# vn210-shield.net
KiCad netlist of a schematic drawn in EAGLE
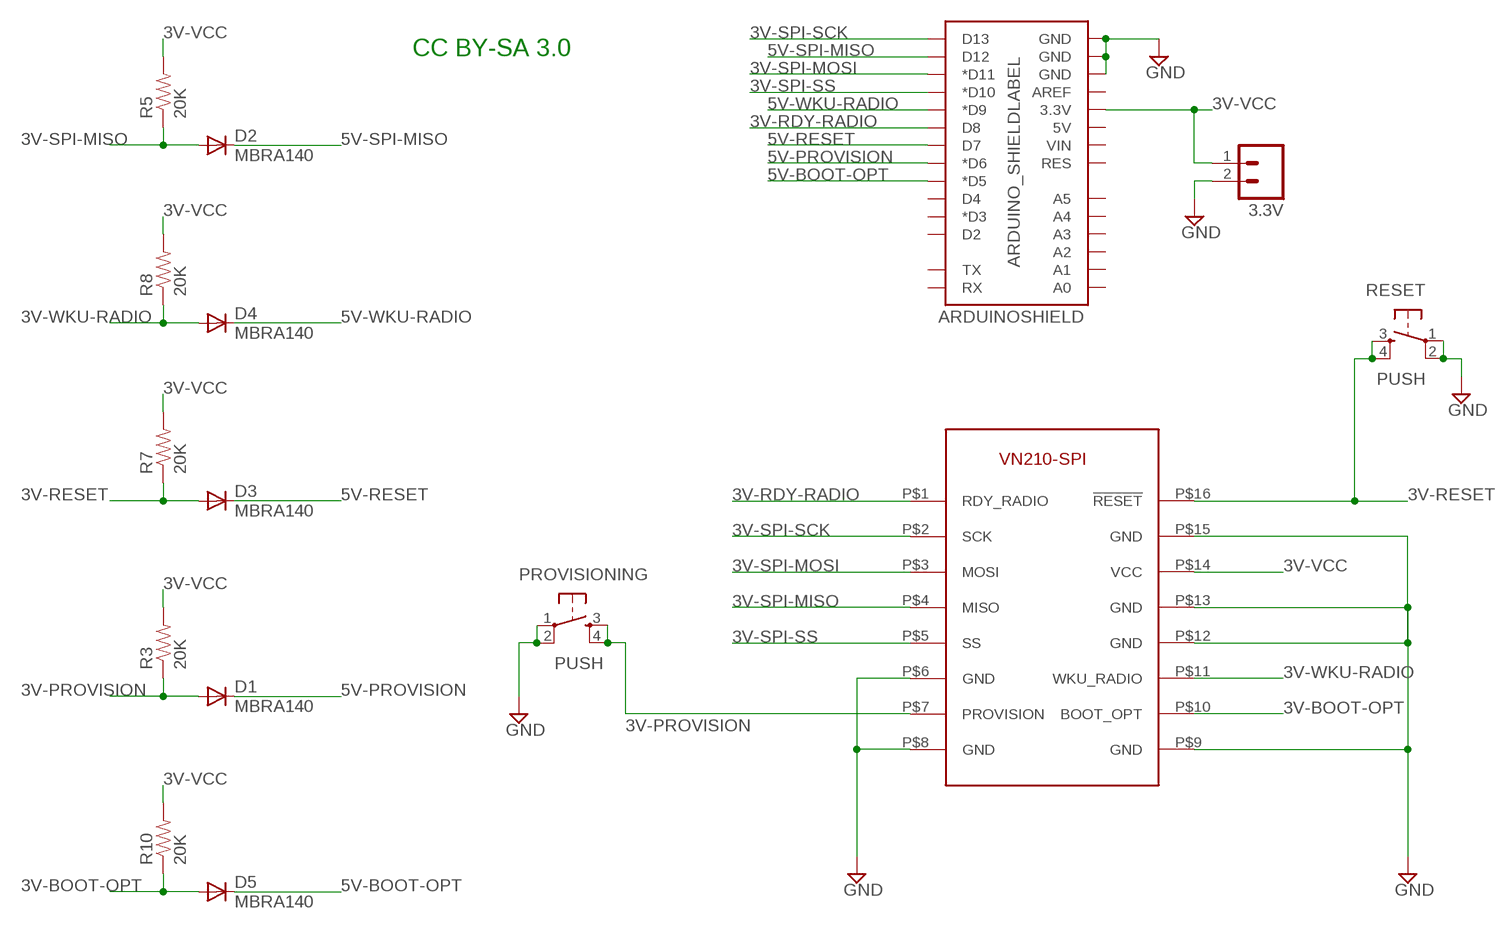
[diagram p0: schematic, sheet 1]

(export (version "E")
  (design (tool "Eeschema 10.0.6"))
  (components
    (comp (ref "3.3V")
      (value "M02LOCK")
      (footprint "eagle-import:1X02_LOCK")
      (libsource (lib "eagle-import") (part "M02LOCK"))
    )
    (comp (ref "ARDUINOSHIELD")
      (value "ARDUINO_SHIELDLABEL")
      (footprint "eagle-import:DUEMILANOVE_SHIELD")
      (libsource (lib "eagle-import") (part "ARDUINO_SHIELDLABEL"))
    )
    (comp (ref "D1")
      (value "MBRA140")
      (footprint "eagle-import:SMA-DIODE_ALT")
      (libsource (lib "eagle-import") (part "DIODESMA-ALT"))
    )
    (comp (ref "D2")
      (value "MBRA140")
      (footprint "eagle-import:SMA-DIODE_ALT")
      (libsource (lib "eagle-import") (part "DIODESMA-ALT"))
    )
    (comp (ref "D3")
      (value "MBRA140")
      (footprint "eagle-import:SMA-DIODE_ALT")
      (libsource (lib "eagle-import") (part "DIODESMA-ALT"))
    )
    (comp (ref "D4")
      (value "MBRA140")
      (footprint "eagle-import:SMA-DIODE_ALT")
      (libsource (lib "eagle-import") (part "DIODESMA-ALT"))
    )
    (comp (ref "D5")
      (value "MBRA140")
      (footprint "eagle-import:SMA-DIODE_ALT")
      (libsource (lib "eagle-import") (part "DIODESMA-ALT"))
    )
    (comp (ref "PROVISIONING")
      (value "PUSH")
      (footprint "eagle-import:TACTILE-PTH")
      (libsource (lib "eagle-import") (part "TAC_SWITCHPTH"))
    )
    (comp (ref "R3")
      (value "20K")
      (footprint "eagle-import:1206")
      (libsource (lib "eagle-import") (part "RESISTOR1206"))
    )
    (comp (ref "R5")
      (value "20K")
      (footprint "eagle-import:1206")
      (libsource (lib "eagle-import") (part "RESISTOR1206"))
    )
    (comp (ref "R7")
      (value "20K")
      (footprint "eagle-import:1206")
      (libsource (lib "eagle-import") (part "RESISTOR1206"))
    )
    (comp (ref "R8")
      (value "20K")
      (footprint "eagle-import:1206")
      (libsource (lib "eagle-import") (part "RESISTOR1206"))
    )
    (comp (ref "R10")
      (value "20K")
      (footprint "eagle-import:1206")
      (libsource (lib "eagle-import") (part "RESISTOR1206"))
    )
    (comp (ref "RESET")
      (value "PUSH")
      (footprint "eagle-import:TACTILE-PTH")
      (libsource (lib "eagle-import") (part "TAC_SWITCHPTH"))
    )
    (comp (ref "U$1")
      (value "VN210-BREAKOUT")
      (footprint "eagle-import:VN210-BREAKOUT")
      (libsource (lib "eagle-import") (part "VN210-BREAKOUT"))
    )
  )
  (nets
    (net (code "1") (name "/3V-BOOT-OPT") (class "Default")
      (node (ref "D5") (pin "A") (pinfunction "A_A") (pintype "passive"))
      (node (ref "R10") (pin "1") (pinfunction "1_1") (pintype "passive"))
      (node (ref "U$1") (pin "P$10") (pinfunction "BOOT_OPT_P$10") (pintype "bidirectional"))
    )
    (net (code "2") (name "/3V-PROVISION") (class "Default")
      (node (ref "D1") (pin "A") (pinfunction "A_A") (pintype "passive"))
      (node (ref "PROVISIONING") (pin "3") (pinfunction "3_3") (pintype "passive"))
      (node (ref "PROVISIONING") (pin "4") (pinfunction "4_4") (pintype "passive"))
      (node (ref "R3") (pin "1") (pinfunction "1_1") (pintype "passive"))
      (node (ref "U$1") (pin "P$7") (pinfunction "PROVISION_P$7") (pintype "bidirectional"))
    )
    (net (code "3") (name "/3V-RDY-RADIO") (class "Default")
      (node (ref "ARDUINOSHIELD") (pin "D8") (pinfunction "D8_D8") (pintype "bidirectional"))
      (node (ref "U$1") (pin "P$1") (pinfunction "RDY_RADIO_P$1") (pintype "bidirectional"))
    )
    (net (code "4") (name "/3V-RESET") (class "Default")
      (node (ref "D3") (pin "A") (pinfunction "A_A") (pintype "passive"))
      (node (ref "R7") (pin "1") (pinfunction "1_1") (pintype "passive"))
      (node (ref "RESET") (pin "3") (pinfunction "3_3") (pintype "passive"))
      (node (ref "RESET") (pin "4") (pinfunction "4_4") (pintype "passive"))
      (node (ref "U$1") (pin "P$16") (pinfunction "~{RESET}_P$16") (pintype "bidirectional"))
    )
    (net (code "5") (name "/3V-SPI-MISO") (class "Default")
      (node (ref "D2") (pin "A") (pinfunction "A_A") (pintype "passive"))
      (node (ref "R5") (pin "1") (pinfunction "1_1") (pintype "passive"))
      (node (ref "U$1") (pin "P$4") (pinfunction "MISO_P$4") (pintype "bidirectional"))
    )
    (net (code "6") (name "/3V-SPI-MOSI") (class "Default")
      (node (ref "ARDUINOSHIELD") (pin "D11") (pinfunction "*D11_D11") (pintype "bidirectional"))
      (node (ref "U$1") (pin "P$3") (pinfunction "MOSI_P$3") (pintype "bidirectional"))
    )
    (net (code "7") (name "/3V-SPI-SCK") (class "Default")
      (node (ref "ARDUINOSHIELD") (pin "D13") (pinfunction "D13_D13") (pintype "bidirectional"))
      (node (ref "U$1") (pin "P$2") (pinfunction "SCK_P$2") (pintype "bidirectional"))
    )
    (net (code "8") (name "/3V-SPI-SS") (class "Default")
      (node (ref "ARDUINOSHIELD") (pin "D10") (pinfunction "*D10_D10") (pintype "bidirectional"))
      (node (ref "U$1") (pin "P$5") (pinfunction "SS_P$5") (pintype "bidirectional"))
    )
    (net (code "9") (name "/3V-VCC") (class "Default")
      (node (ref "3.3V") (pin "1") (pinfunction "1_1") (pintype "passive"))
      (node (ref "ARDUINOSHIELD") (pin "3.3V") (pinfunction "3.3V_3.3V") (pintype "bidirectional"))
      (node (ref "R10") (pin "2") (pinfunction "2_2") (pintype "passive"))
      (node (ref "R3") (pin "2") (pinfunction "2_2") (pintype "passive"))
      (node (ref "R5") (pin "2") (pinfunction "2_2") (pintype "passive"))
      (node (ref "R7") (pin "2") (pinfunction "2_2") (pintype "passive"))
      (node (ref "R8") (pin "2") (pinfunction "2_2") (pintype "passive"))
      (node (ref "U$1") (pin "P$14") (pinfunction "VCC_P$14") (pintype "bidirectional"))
    )
    (net (code "10") (name "/3V-WKU-RADIO") (class "Default")
      (node (ref "D4") (pin "A") (pinfunction "A_A") (pintype "passive"))
      (node (ref "R8") (pin "1") (pinfunction "1_1") (pintype "passive"))
      (node (ref "U$1") (pin "P$11") (pinfunction "WKU_RADIO_P$11") (pintype "bidirectional"))
    )
    (net (code "11") (name "/5V-BOOT-OPT") (class "Default")
      (node (ref "ARDUINOSHIELD") (pin "D5") (pinfunction "*D5_D5") (pintype "bidirectional"))
      (node (ref "D5") (pin "C") (pinfunction "C_C") (pintype "passive"))
    )
    (net (code "12") (name "/5V-PROVISION") (class "Default")
      (node (ref "ARDUINOSHIELD") (pin "D6") (pinfunction "*D6_D6") (pintype "bidirectional"))
      (node (ref "D1") (pin "C") (pinfunction "C_C") (pintype "passive"))
    )
    (net (code "13") (name "/5V-RESET") (class "Default")
      (node (ref "ARDUINOSHIELD") (pin "D7") (pinfunction "D7_D7") (pintype "bidirectional"))
      (node (ref "D3") (pin "C") (pinfunction "C_C") (pintype "passive"))
    )
    (net (code "14") (name "/5V-SPI-MISO") (class "Default")
      (node (ref "ARDUINOSHIELD") (pin "D12") (pinfunction "D12_D12") (pintype "bidirectional"))
      (node (ref "D2") (pin "C") (pinfunction "C_C") (pintype "passive"))
    )
    (net (code "15") (name "/5V-WKU-RADIO") (class "Default")
      (node (ref "ARDUINOSHIELD") (pin "D9") (pinfunction "*D9_D9") (pintype "bidirectional"))
      (node (ref "D4") (pin "C") (pinfunction "C_C") (pintype "passive"))
    )
    (net (code "16") (name "GND") (class "Default")
      (node (ref "3.3V") (pin "2") (pinfunction "2_2") (pintype "passive"))
      (node (ref "ARDUINOSHIELD") (pin "GND@0") (pinfunction "GND_GND@0") (pintype "bidirectional"))
      (node (ref "ARDUINOSHIELD") (pin "GND@1") (pinfunction "GND_GND@1") (pintype "bidirectional"))
      (node (ref "ARDUINOSHIELD") (pin "GND@2") (pinfunction "GND_GND@2") (pintype "bidirectional"))
      (node (ref "PROVISIONING") (pin "1") (pinfunction "1_1") (pintype "passive"))
      (node (ref "PROVISIONING") (pin "2") (pinfunction "2_2") (pintype "passive"))
      (node (ref "RESET") (pin "1") (pinfunction "1_1") (pintype "passive"))
      (node (ref "RESET") (pin "2") (pinfunction "2_2") (pintype "passive"))
      (node (ref "U$1") (pin "P$12") (pinfunction "GND_P$12") (pintype "bidirectional"))
      (node (ref "U$1") (pin "P$13") (pinfunction "GND_P$13") (pintype "bidirectional"))
      (node (ref "U$1") (pin "P$15") (pinfunction "GND_P$15") (pintype "bidirectional"))
      (node (ref "U$1") (pin "P$6") (pinfunction "GND_P$6") (pintype "bidirectional"))
      (node (ref "U$1") (pin "P$8") (pinfunction "GND_P$8") (pintype "bidirectional"))
      (node (ref "U$1") (pin "P$9") (pinfunction "GND_P$9") (pintype "bidirectional"))
    )
    (net (code "17") (name "unconnected-(ARDUINOSHIELD-*D3-PadD3)") (class "Default")
      (node (ref "ARDUINOSHIELD") (pin "D3") (pinfunction "*D3_D3") (pintype "bidirectional"))
    )
    (net (code "18") (name "unconnected-(ARDUINOSHIELD-Pad5V)") (class "Default")
      (node (ref "ARDUINOSHIELD") (pin "5V") (pinfunction "5V_5V") (pintype "bidirectional"))
    )
    (net (code "19") (name "unconnected-(ARDUINOSHIELD-PadA0)") (class "Default")
      (node (ref "ARDUINOSHIELD") (pin "A0") (pinfunction "A0_A0") (pintype "bidirectional"))
    )
    (net (code "20") (name "unconnected-(ARDUINOSHIELD-PadA1)") (class "Default")
      (node (ref "ARDUINOSHIELD") (pin "A1") (pinfunction "A1_A1") (pintype "bidirectional"))
    )
    (net (code "21") (name "unconnected-(ARDUINOSHIELD-PadA2)") (class "Default")
      (node (ref "ARDUINOSHIELD") (pin "A2") (pinfunction "A2_A2") (pintype "bidirectional"))
    )
    (net (code "22") (name "unconnected-(ARDUINOSHIELD-PadA3)") (class "Default")
      (node (ref "ARDUINOSHIELD") (pin "A3") (pinfunction "A3_A3") (pintype "bidirectional"))
    )
    (net (code "23") (name "unconnected-(ARDUINOSHIELD-PadA4)") (class "Default")
      (node (ref "ARDUINOSHIELD") (pin "A4") (pinfunction "A4_A4") (pintype "bidirectional"))
    )
    (net (code "24") (name "unconnected-(ARDUINOSHIELD-PadA5)") (class "Default")
      (node (ref "ARDUINOSHIELD") (pin "A5") (pinfunction "A5_A5") (pintype "bidirectional"))
    )
    (net (code "25") (name "unconnected-(ARDUINOSHIELD-PadAREF)") (class "Default")
      (node (ref "ARDUINOSHIELD") (pin "AREF") (pinfunction "AREF_AREF") (pintype "bidirectional"))
    )
    (net (code "26") (name "unconnected-(ARDUINOSHIELD-PadD2)") (class "Default")
      (node (ref "ARDUINOSHIELD") (pin "D2") (pinfunction "D2_D2") (pintype "bidirectional"))
    )
    (net (code "27") (name "unconnected-(ARDUINOSHIELD-PadD4)") (class "Default")
      (node (ref "ARDUINOSHIELD") (pin "D4") (pinfunction "D4_D4") (pintype "bidirectional"))
    )
    (net (code "28") (name "unconnected-(ARDUINOSHIELD-PadRES)") (class "Default")
      (node (ref "ARDUINOSHIELD") (pin "RES") (pinfunction "RES_RES") (pintype "bidirectional"))
    )
    (net (code "29") (name "unconnected-(ARDUINOSHIELD-PadRX)") (class "Default")
      (node (ref "ARDUINOSHIELD") (pin "RX") (pinfunction "RX_RX") (pintype "bidirectional"))
    )
    (net (code "30") (name "unconnected-(ARDUINOSHIELD-PadTX)") (class "Default")
      (node (ref "ARDUINOSHIELD") (pin "TX") (pinfunction "TX_TX") (pintype "bidirectional"))
    )
    (net (code "31") (name "unconnected-(ARDUINOSHIELD-PadVIN)") (class "Default")
      (node (ref "ARDUINOSHIELD") (pin "VIN") (pinfunction "VIN_VIN") (pintype "bidirectional"))
    )
  )
)
